# Power_module.net
KiCad netlist of a schematic drawn in EAGLE
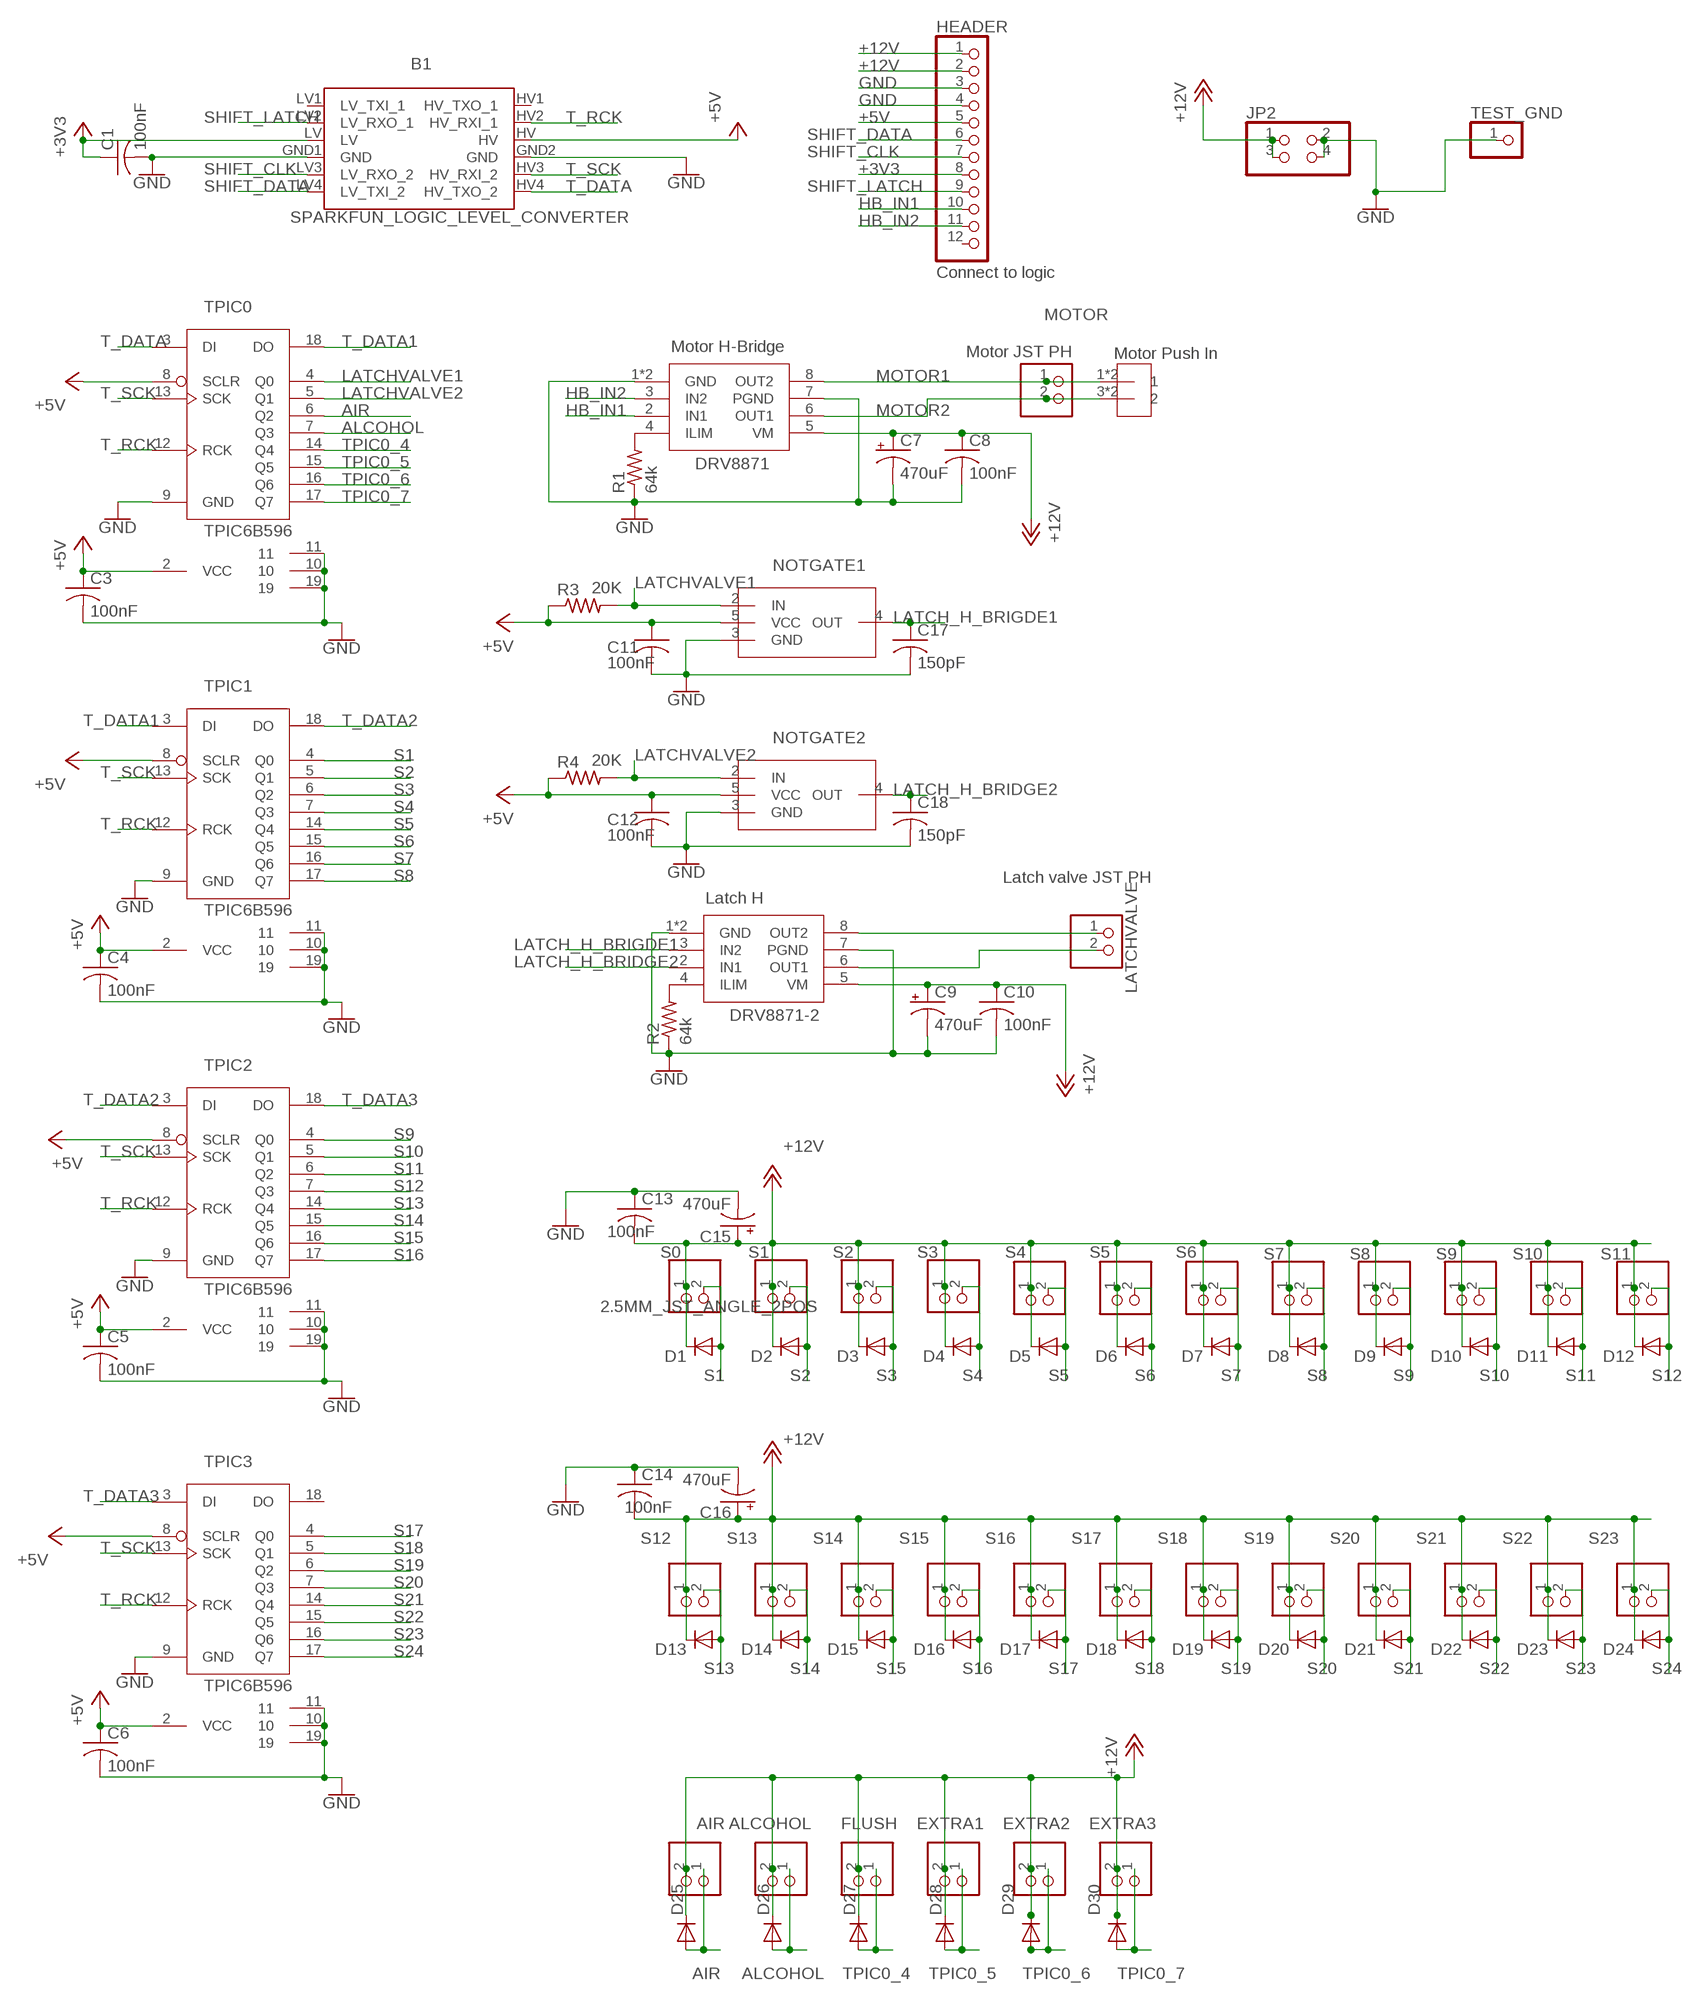
[diagram p0: schematic, sheet 1]

(export (version "E")
  (design (tool "Eeschema 10.0.6"))
  (components
    (comp (ref "AIR")
      (value "2.5MM_JST_UP_2POS")
      (footprint "eagle-import:JST_2POS_2.5MM_UP")
      (libsource (lib "eagle-import") (part "2.5MM_JST_UP_2POS"))
    )
    (comp (ref "ALCOHOL")
      (value "2.5MM_JST_UP_2POS")
      (footprint "eagle-import:JST_2POS_2.5MM_UP")
      (libsource (lib "eagle-import") (part "2.5MM_JST_UP_2POS"))
    )
    (comp (ref "B1")
      (value "SPARKFUN_LOGIC_LEVEL_CONVERTER")
      (footprint "eagle-import:SPARKFUN_LOGIC_LEVEL_CONVERTER")
      (libsource (lib "eagle-import") (part "SPARKFUN_LOGIC_LEVEL_CONVERTER"))
    )
    (comp (ref "C1")
      (value "100nF")
      (footprint "eagle-import:C050-024X044")
      (libsource (lib "eagle-import") (part "C-US050-024X044"))
    )
    (comp (ref "C3")
      (value "100nF")
      (footprint "eagle-import:C050-024X044")
      (libsource (lib "eagle-import") (part "C-US050-024X044"))
    )
    (comp (ref "C4")
      (value "100nF")
      (footprint "eagle-import:C050-024X044")
      (libsource (lib "eagle-import") (part "C-US050-024X044"))
    )
    (comp (ref "C5")
      (value "100nF")
      (footprint "eagle-import:C050-024X044")
      (libsource (lib "eagle-import") (part "C-US050-024X044"))
    )
    (comp (ref "C6")
      (value "100nF")
      (footprint "eagle-import:C050-024X044")
      (libsource (lib "eagle-import") (part "C-US050-024X044"))
    )
    (comp (ref "C7")
      (value "470uF")
      (footprint "eagle-import:140CLH-0810")
      (libsource (lib "eagle-import") (part "CPOL-US140CLH-0810"))
    )
    (comp (ref "C8")
      (value "100nF")
      (footprint "eagle-import:C050-024X044")
      (libsource (lib "eagle-import") (part "C-US050-024X044"))
    )
    (comp (ref "C9")
      (value "470uF")
      (footprint "eagle-import:140CLH-0810")
      (libsource (lib "eagle-import") (part "CPOL-US140CLH-0810"))
    )
    (comp (ref "C10")
      (value "100nF")
      (footprint "eagle-import:C050-024X044")
      (libsource (lib "eagle-import") (part "C-US050-024X044"))
    )
    (comp (ref "C11")
      (value "100nF")
      (footprint "eagle-import:C1206")
      (libsource (lib "eagle-import") (part "C-USC1206"))
    )
    (comp (ref "C12")
      (value "100nF")
      (footprint "eagle-import:C1206")
      (libsource (lib "eagle-import") (part "C-USC1206"))
    )
    (comp (ref "C13")
      (value "100nF")
      (footprint "eagle-import:C050-024X044")
      (libsource (lib "eagle-import") (part "C-US050-024X044"))
    )
    (comp (ref "C14")
      (value "100nF")
      (footprint "eagle-import:C050-024X044")
      (libsource (lib "eagle-import") (part "C-US050-024X044"))
    )
    (comp (ref "C15")
      (value "470uF")
      (footprint "eagle-import:140CLH-0810")
      (libsource (lib "eagle-import") (part "CPOL-US140CLH-0810"))
    )
    (comp (ref "C16")
      (value "470uF")
      (footprint "eagle-import:140CLH-0810")
      (libsource (lib "eagle-import") (part "CPOL-US140CLH-0810"))
    )
    (comp (ref "C17")
      (value "150pF")
      (footprint "eagle-import:C050-024X044")
      (libsource (lib "eagle-import") (part "C-US050-024X044"))
    )
    (comp (ref "C18")
      (value "150pF")
      (footprint "eagle-import:C050-024X044")
      (libsource (lib "eagle-import") (part "C-US050-024X044"))
    )
    (comp (ref "D1")
      (value "DIODESOD-123")
      (footprint "eagle-import:SOD-123")
      (libsource (lib "eagle-import") (part "DIODESOD-123"))
    )
    (comp (ref "D2")
      (value "DIODESOD-123")
      (footprint "eagle-import:SOD-123")
      (libsource (lib "eagle-import") (part "DIODESOD-123"))
    )
    (comp (ref "D3")
      (value "DIODESOD-123")
      (footprint "eagle-import:SOD-123")
      (libsource (lib "eagle-import") (part "DIODESOD-123"))
    )
    (comp (ref "D4")
      (value "DIODESOD-123")
      (footprint "eagle-import:SOD-123")
      (libsource (lib "eagle-import") (part "DIODESOD-123"))
    )
    (comp (ref "D5")
      (value "DIODESOD-123")
      (footprint "eagle-import:SOD-123")
      (libsource (lib "eagle-import") (part "DIODESOD-123"))
    )
    (comp (ref "D6")
      (value "DIODESOD-123")
      (footprint "eagle-import:SOD-123")
      (libsource (lib "eagle-import") (part "DIODESOD-123"))
    )
    (comp (ref "D7")
      (value "DIODESOD-123")
      (footprint "eagle-import:SOD-123")
      (libsource (lib "eagle-import") (part "DIODESOD-123"))
    )
    (comp (ref "D8")
      (value "DIODESOD-123")
      (footprint "eagle-import:SOD-123")
      (libsource (lib "eagle-import") (part "DIODESOD-123"))
    )
    (comp (ref "D9")
      (value "DIODESOD-123")
      (footprint "eagle-import:SOD-123")
      (libsource (lib "eagle-import") (part "DIODESOD-123"))
    )
    (comp (ref "D10")
      (value "DIODESOD-123")
      (footprint "eagle-import:SOD-123")
      (libsource (lib "eagle-import") (part "DIODESOD-123"))
    )
    (comp (ref "D11")
      (value "DIODESOD-123")
      (footprint "eagle-import:SOD-123")
      (libsource (lib "eagle-import") (part "DIODESOD-123"))
    )
    (comp (ref "D12")
      (value "DIODESOD-123")
      (footprint "eagle-import:SOD-123")
      (libsource (lib "eagle-import") (part "DIODESOD-123"))
    )
    (comp (ref "D13")
      (value "DIODESOD-123")
      (footprint "eagle-import:SOD-123")
      (libsource (lib "eagle-import") (part "DIODESOD-123"))
    )
    (comp (ref "D14")
      (value "DIODESOD-123")
      (footprint "eagle-import:SOD-123")
      (libsource (lib "eagle-import") (part "DIODESOD-123"))
    )
    (comp (ref "D15")
      (value "DIODESOD-123")
      (footprint "eagle-import:SOD-123")
      (libsource (lib "eagle-import") (part "DIODESOD-123"))
    )
    (comp (ref "D16")
      (value "DIODESOD-123")
      (footprint "eagle-import:SOD-123")
      (libsource (lib "eagle-import") (part "DIODESOD-123"))
    )
    (comp (ref "D17")
      (value "DIODESOD-123")
      (footprint "eagle-import:SOD-123")
      (libsource (lib "eagle-import") (part "DIODESOD-123"))
    )
    (comp (ref "D18")
      (value "DIODESOD-123")
      (footprint "eagle-import:SOD-123")
      (libsource (lib "eagle-import") (part "DIODESOD-123"))
    )
    (comp (ref "D19")
      (value "DIODESOD-123")
      (footprint "eagle-import:SOD-123")
      (libsource (lib "eagle-import") (part "DIODESOD-123"))
    )
    (comp (ref "D20")
      (value "DIODESOD-123")
      (footprint "eagle-import:SOD-123")
      (libsource (lib "eagle-import") (part "DIODESOD-123"))
    )
    (comp (ref "D21")
      (value "DIODESOD-123")
      (footprint "eagle-import:SOD-123")
      (libsource (lib "eagle-import") (part "DIODESOD-123"))
    )
    (comp (ref "D22")
      (value "DIODESOD-123")
      (footprint "eagle-import:SOD-123")
      (libsource (lib "eagle-import") (part "DIODESOD-123"))
    )
    (comp (ref "D23")
      (value "DIODESOD-123")
      (footprint "eagle-import:SOD-123")
      (libsource (lib "eagle-import") (part "DIODESOD-123"))
    )
    (comp (ref "D24")
      (value "DIODESOD-123")
      (footprint "eagle-import:SOD-123")
      (libsource (lib "eagle-import") (part "DIODESOD-123"))
    )
    (comp (ref "D25")
      (value "DIODESOD-123")
      (footprint "eagle-import:SOD-123")
      (libsource (lib "eagle-import") (part "DIODESOD-123"))
    )
    (comp (ref "D26")
      (value "DIODESOD-123")
      (footprint "eagle-import:SOD-123")
      (libsource (lib "eagle-import") (part "DIODESOD-123"))
    )
    (comp (ref "D27")
      (value "DIODESOD-123")
      (footprint "eagle-import:SOD-123")
      (libsource (lib "eagle-import") (part "DIODESOD-123"))
    )
    (comp (ref "D28")
      (value "DIODESOD-123")
      (footprint "eagle-import:SOD-123")
      (libsource (lib "eagle-import") (part "DIODESOD-123"))
    )
    (comp (ref "D29")
      (value "DIODESOD-123")
      (footprint "eagle-import:SOD-123")
      (libsource (lib "eagle-import") (part "DIODESOD-123"))
    )
    (comp (ref "D30")
      (value "DIODESOD-123")
      (footprint "eagle-import:SOD-123")
      (libsource (lib "eagle-import") (part "DIODESOD-123"))
    )
    (comp (ref "DRV8871")
      (value "Motor H-Bridge")
      (footprint "eagle-import:SOP8")
      (libsource (lib "eagle-import") (part "DRV8871"))
    )
    (comp (ref "DRV8871-2")
      (value "Latch H")
      (footprint "eagle-import:SOP8")
      (libsource (lib "eagle-import") (part "DRV8871"))
    )
    (comp (ref "EXTRA1")
      (value "2.5MM_JST_UP_2POS")
      (footprint "eagle-import:JST_2POS_2.5MM_UP")
      (libsource (lib "eagle-import") (part "2.5MM_JST_UP_2POS"))
    )
    (comp (ref "EXTRA2")
      (value "2.5MM_JST_UP_2POS")
      (footprint "eagle-import:JST_2POS_2.5MM_UP")
      (libsource (lib "eagle-import") (part "2.5MM_JST_UP_2POS"))
    )
    (comp (ref "EXTRA3")
      (value "2.5MM_JST_UP_2POS")
      (footprint "eagle-import:JST_2POS_2.5MM_UP")
      (libsource (lib "eagle-import") (part "2.5MM_JST_UP_2POS"))
    )
    (comp (ref "FLUSH")
      (value "2.5MM_JST_UP_2POS")
      (footprint "eagle-import:JST_2POS_2.5MM_UP")
      (libsource (lib "eagle-import") (part "2.5MM_JST_UP_2POS"))
    )
    (comp (ref "HEADER")
      (value "Connect to logic")
      (footprint "eagle-import:1X12")
      (libsource (lib "eagle-import") (part "PINHD-1X12"))
    )
    (comp (ref "JP2")
      (value "PINHD-2X2")
      (footprint "eagle-import:2X02")
      (libsource (lib "eagle-import") (part "PINHD-2X2"))
    )
    (comp (ref "LATCHVALVE")
      (value "Latch valve JST PH")
      (footprint "eagle-import:JST_2POS_2.5MM_UP")
      (libsource (lib "eagle-import") (part "2.5MM_JST_UP_2POS"))
    )
    (comp (ref "MOTOR")
      (value "Motor JST PH")
      (footprint "eagle-import:JST_2POS_2.5MM_UP")
      (libsource (lib "eagle-import") (part "2.5MM_JST_UP_2POS"))
    )
    (comp (ref "NOTGATE1")
      (value "NOT_GATE")
      (footprint "eagle-import:SOT753")
      (libsource (lib "eagle-import") (part "NOT_GATE"))
    )
    (comp (ref "NOTGATE2")
      (value "NOT_GATE")
      (footprint "eagle-import:SOT753")
      (libsource (lib "eagle-import") (part "NOT_GATE"))
    )
    (comp (ref "R1")
      (value "64k")
      (footprint "eagle-import:0204_5")
      (libsource (lib "eagle-import") (part "R-US_0204/5"))
    )
    (comp (ref "R2")
      (value "64k")
      (footprint "eagle-import:0204_5")
      (libsource (lib "eagle-import") (part "R-US_0204/5"))
    )
    (comp (ref "R3")
      (value "20K")
      (footprint "eagle-import:R1206")
      (libsource (lib "eagle-import") (part "R-US_R1206"))
    )
    (comp (ref "R4")
      (value "20K")
      (footprint "eagle-import:R1206")
      (libsource (lib "eagle-import") (part "R-US_R1206"))
    )
    (comp (ref "S0")
      (value "2.5MM_JST_ANGLE_2POS")
      (footprint "eagle-import:JST_2POS_2.5MM_ANGLE")
      (libsource (lib "eagle-import") (part "2.5MM_JST_ANGLE_2POS"))
    )
    (comp (ref "S1")
      (value "2.5MM_JST_ANGLE_2POS")
      (footprint "eagle-import:JST_2POS_2.5MM_ANGLE")
      (libsource (lib "eagle-import") (part "2.5MM_JST_ANGLE_2POS"))
    )
    (comp (ref "S2")
      (value "2.5MM_JST_ANGLE_2POS")
      (footprint "eagle-import:JST_2POS_2.5MM_ANGLE")
      (libsource (lib "eagle-import") (part "2.5MM_JST_ANGLE_2POS"))
    )
    (comp (ref "S3")
      (value "2.5MM_JST_ANGLE_2POS")
      (footprint "eagle-import:JST_2POS_2.5MM_ANGLE")
      (libsource (lib "eagle-import") (part "2.5MM_JST_ANGLE_2POS"))
    )
    (comp (ref "S4")
      (value "2.5MM_JST_ANGLE_2POS")
      (footprint "eagle-import:JST_2POS_2.5MM_ANGLE")
      (libsource (lib "eagle-import") (part "2.5MM_JST_ANGLE_2POS"))
    )
    (comp (ref "S5")
      (value "2.5MM_JST_ANGLE_2POS")
      (footprint "eagle-import:JST_2POS_2.5MM_ANGLE")
      (libsource (lib "eagle-import") (part "2.5MM_JST_ANGLE_2POS"))
    )
    (comp (ref "S6")
      (value "2.5MM_JST_ANGLE_2POS")
      (footprint "eagle-import:JST_2POS_2.5MM_ANGLE")
      (libsource (lib "eagle-import") (part "2.5MM_JST_ANGLE_2POS"))
    )
    (comp (ref "S7")
      (value "2.5MM_JST_ANGLE_2POS")
      (footprint "eagle-import:JST_2POS_2.5MM_ANGLE")
      (libsource (lib "eagle-import") (part "2.5MM_JST_ANGLE_2POS"))
    )
    (comp (ref "S8")
      (value "2.5MM_JST_ANGLE_2POS")
      (footprint "eagle-import:JST_2POS_2.5MM_ANGLE")
      (libsource (lib "eagle-import") (part "2.5MM_JST_ANGLE_2POS"))
    )
    (comp (ref "S9")
      (value "2.5MM_JST_ANGLE_2POS")
      (footprint "eagle-import:JST_2POS_2.5MM_ANGLE")
      (libsource (lib "eagle-import") (part "2.5MM_JST_ANGLE_2POS"))
    )
    (comp (ref "S10")
      (value "2.5MM_JST_ANGLE_2POS")
      (footprint "eagle-import:JST_2POS_2.5MM_ANGLE")
      (libsource (lib "eagle-import") (part "2.5MM_JST_ANGLE_2POS"))
    )
    (comp (ref "S11")
      (value "2.5MM_JST_ANGLE_2POS")
      (footprint "eagle-import:JST_2POS_2.5MM_ANGLE")
      (libsource (lib "eagle-import") (part "2.5MM_JST_ANGLE_2POS"))
    )
    (comp (ref "S12")
      (value "2.5MM_JST_ANGLE_2POS")
      (footprint "eagle-import:JST_2POS_2.5MM_ANGLE")
      (libsource (lib "eagle-import") (part "2.5MM_JST_ANGLE_2POS"))
    )
    (comp (ref "S13")
      (value "2.5MM_JST_ANGLE_2POS")
      (footprint "eagle-import:JST_2POS_2.5MM_ANGLE")
      (libsource (lib "eagle-import") (part "2.5MM_JST_ANGLE_2POS"))
    )
    (comp (ref "S14")
      (value "2.5MM_JST_ANGLE_2POS")
      (footprint "eagle-import:JST_2POS_2.5MM_ANGLE")
      (libsource (lib "eagle-import") (part "2.5MM_JST_ANGLE_2POS"))
    )
    (comp (ref "S15")
      (value "2.5MM_JST_ANGLE_2POS")
      (footprint "eagle-import:JST_2POS_2.5MM_ANGLE")
      (libsource (lib "eagle-import") (part "2.5MM_JST_ANGLE_2POS"))
    )
    (comp (ref "S16")
      (value "2.5MM_JST_ANGLE_2POS")
      (footprint "eagle-import:JST_2POS_2.5MM_ANGLE")
      (libsource (lib "eagle-import") (part "2.5MM_JST_ANGLE_2POS"))
    )
    (comp (ref "S17")
      (value "2.5MM_JST_ANGLE_2POS")
      (footprint "eagle-import:JST_2POS_2.5MM_ANGLE")
      (libsource (lib "eagle-import") (part "2.5MM_JST_ANGLE_2POS"))
    )
    (comp (ref "S18")
      (value "2.5MM_JST_ANGLE_2POS")
      (footprint "eagle-import:JST_2POS_2.5MM_ANGLE")
      (libsource (lib "eagle-import") (part "2.5MM_JST_ANGLE_2POS"))
    )
    (comp (ref "S19")
      (value "2.5MM_JST_ANGLE_2POS")
      (footprint "eagle-import:JST_2POS_2.5MM_ANGLE")
      (libsource (lib "eagle-import") (part "2.5MM_JST_ANGLE_2POS"))
    )
    (comp (ref "S20")
      (value "2.5MM_JST_ANGLE_2POS")
      (footprint "eagle-import:JST_2POS_2.5MM_ANGLE")
      (libsource (lib "eagle-import") (part "2.5MM_JST_ANGLE_2POS"))
    )
    (comp (ref "S21")
      (value "2.5MM_JST_ANGLE_2POS")
      (footprint "eagle-import:JST_2POS_2.5MM_ANGLE")
      (libsource (lib "eagle-import") (part "2.5MM_JST_ANGLE_2POS"))
    )
    (comp (ref "S22")
      (value "2.5MM_JST_ANGLE_2POS")
      (footprint "eagle-import:JST_2POS_2.5MM_ANGLE")
      (libsource (lib "eagle-import") (part "2.5MM_JST_ANGLE_2POS"))
    )
    (comp (ref "S23")
      (value "2.5MM_JST_ANGLE_2POS")
      (footprint "eagle-import:JST_2POS_2.5MM_ANGLE")
      (libsource (lib "eagle-import") (part "2.5MM_JST_ANGLE_2POS"))
    )
    (comp (ref "TEST_GND")
      (value "PINHD-1X1")
      (footprint "eagle-import:1X01")
      (libsource (lib "eagle-import") (part "PINHD-1X1"))
    )
    (comp (ref "TPIC0")
      (value "TPIC6B596")
      (footprint "eagle-import:DIP20")
      (libsource (lib "eagle-import") (part "TPIC6B596"))
    )
    (comp (ref "TPIC1")
      (value "TPIC6B596")
      (footprint "eagle-import:DIP20")
      (libsource (lib "eagle-import") (part "TPIC6B596"))
    )
    (comp (ref "TPIC2")
      (value "TPIC6B596")
      (footprint "eagle-import:DIP20")
      (libsource (lib "eagle-import") (part "TPIC6B596"))
    )
    (comp (ref "TPIC3")
      (value "TPIC6B596")
      (footprint "eagle-import:DIP20")
      (libsource (lib "eagle-import") (part "TPIC6B596"))
    )
    (comp (ref "U$1")
      (value "Motor Push In")
      (footprint "eagle-import:3.5MM_DIP2")
      (libsource (lib "eagle-import") (part "PUSH_IN_2"))
    )
  )
  (nets
    (net (code "1") (name "+3V3") (class "Default")
      (node (ref "B1") (pin "LV") (pinfunction "LV_LV") (pintype "power_in"))
      (node (ref "C1") (pin "1") (pinfunction "1_1") (pintype "passive"))
      (node (ref "HEADER") (pin "8") (pinfunction "8_8") (pintype "passive"))
    )
    (net (code "2") (name "+5V") (class "Default")
      (node (ref "B1") (pin "HV") (pinfunction "HV_HV") (pintype "power_in"))
      (node (ref "C11") (pin "1") (pinfunction "1_1") (pintype "passive"))
      (node (ref "C12") (pin "1") (pinfunction "1_1") (pintype "passive"))
      (node (ref "C3") (pin "1") (pinfunction "1_1") (pintype "passive"))
      (node (ref "C4") (pin "1") (pinfunction "1_1") (pintype "passive"))
      (node (ref "C5") (pin "1") (pinfunction "1_1") (pintype "passive"))
      (node (ref "C6") (pin "1") (pinfunction "1_1") (pintype "passive"))
      (node (ref "HEADER") (pin "5") (pinfunction "5_5") (pintype "passive"))
      (node (ref "NOTGATE1") (pin "5") (pinfunction "VCC_5") (pintype "bidirectional"))
      (node (ref "NOTGATE2") (pin "5") (pinfunction "VCC_5") (pintype "bidirectional"))
      (node (ref "R3") (pin "1") (pinfunction "1_1") (pintype "passive"))
      (node (ref "R4") (pin "1") (pinfunction "1_1") (pintype "passive"))
      (node (ref "TPIC0") (pin "2") (pinfunction "VCC_2") (pintype "bidirectional"))
      (node (ref "TPIC0") (pin "8") (pinfunction "SCLR_8") (pintype "bidirectional"))
      (node (ref "TPIC1") (pin "2") (pinfunction "VCC_2") (pintype "bidirectional"))
      (node (ref "TPIC1") (pin "8") (pinfunction "SCLR_8") (pintype "bidirectional"))
      (node (ref "TPIC2") (pin "2") (pinfunction "VCC_2") (pintype "bidirectional"))
      (node (ref "TPIC2") (pin "8") (pinfunction "SCLR_8") (pintype "bidirectional"))
      (node (ref "TPIC3") (pin "2") (pinfunction "VCC_2") (pintype "bidirectional"))
      (node (ref "TPIC3") (pin "8") (pinfunction "SCLR_8") (pintype "bidirectional"))
    )
    (net (code "3") (name "+12V") (class "Default")
      (node (ref "AIR") (pin "2") (pinfunction "2_2") (pintype "bidirectional"))
      (node (ref "ALCOHOL") (pin "2") (pinfunction "2_2") (pintype "bidirectional"))
      (node (ref "C10") (pin "1") (pinfunction "1_1") (pintype "passive"))
      (node (ref "C13") (pin "2") (pinfunction "2_2") (pintype "passive"))
      (node (ref "C14") (pin "2") (pinfunction "2_2") (pintype "passive"))
      (node (ref "C15") (pin "+") (pinfunction "+_+") (pintype "passive"))
      (node (ref "C16") (pin "+") (pinfunction "+_+") (pintype "passive"))
      (node (ref "C7") (pin "+") (pinfunction "+_+") (pintype "passive"))
      (node (ref "C8") (pin "1") (pinfunction "1_1") (pintype "passive"))
      (node (ref "C9") (pin "+") (pinfunction "+_+") (pintype "passive"))
      (node (ref "D1") (pin "C") (pinfunction "C_C") (pintype "passive"))
      (node (ref "D10") (pin "C") (pinfunction "C_C") (pintype "passive"))
      (node (ref "D11") (pin "C") (pinfunction "C_C") (pintype "passive"))
      (node (ref "D12") (pin "C") (pinfunction "C_C") (pintype "passive"))
      (node (ref "D13") (pin "C") (pinfunction "C_C") (pintype "passive"))
      (node (ref "D14") (pin "C") (pinfunction "C_C") (pintype "passive"))
      (node (ref "D15") (pin "C") (pinfunction "C_C") (pintype "passive"))
      (node (ref "D16") (pin "C") (pinfunction "C_C") (pintype "passive"))
      (node (ref "D17") (pin "C") (pinfunction "C_C") (pintype "passive"))
      (node (ref "D18") (pin "C") (pinfunction "C_C") (pintype "passive"))
      (node (ref "D19") (pin "C") (pinfunction "C_C") (pintype "passive"))
      (node (ref "D2") (pin "C") (pinfunction "C_C") (pintype "passive"))
      (node (ref "D20") (pin "C") (pinfunction "C_C") (pintype "passive"))
      (node (ref "D21") (pin "C") (pinfunction "C_C") (pintype "passive"))
      (node (ref "D22") (pin "C") (pinfunction "C_C") (pintype "passive"))
      (node (ref "D23") (pin "C") (pinfunction "C_C") (pintype "passive"))
      (node (ref "D24") (pin "C") (pinfunction "C_C") (pintype "passive"))
      (node (ref "D25") (pin "C") (pinfunction "C_C") (pintype "passive"))
      (node (ref "D26") (pin "C") (pinfunction "C_C") (pintype "passive"))
      (node (ref "D27") (pin "C") (pinfunction "C_C") (pintype "passive"))
      (node (ref "D28") (pin "C") (pinfunction "C_C") (pintype "passive"))
      (node (ref "D29") (pin "C") (pinfunction "C_C") (pintype "passive"))
      (node (ref "D3") (pin "C") (pinfunction "C_C") (pintype "passive"))
      (node (ref "D30") (pin "C") (pinfunction "C_C") (pintype "passive"))
      (node (ref "D4") (pin "C") (pinfunction "C_C") (pintype "passive"))
      (node (ref "D5") (pin "C") (pinfunction "C_C") (pintype "passive"))
      (node (ref "D6") (pin "C") (pinfunction "C_C") (pintype "passive"))
      (node (ref "D7") (pin "C") (pinfunction "C_C") (pintype "passive"))
      (node (ref "D8") (pin "C") (pinfunction "C_C") (pintype "passive"))
      (node (ref "D9") (pin "C") (pinfunction "C_C") (pintype "passive"))
      (node (ref "DRV8871") (pin "5") (pinfunction "VM_5") (pintype "bidirectional"))
      (node (ref "DRV8871-2") (pin "5") (pinfunction "VM_5") (pintype "bidirectional"))
      (node (ref "EXTRA1") (pin "2") (pinfunction "2_2") (pintype "bidirectional"))
      (node (ref "EXTRA2") (pin "2") (pinfunction "2_2") (pintype "bidirectional"))
      (node (ref "EXTRA3") (pin "2") (pinfunction "2_2") (pintype "bidirectional"))
      (node (ref "FLUSH") (pin "2") (pinfunction "2_2") (pintype "bidirectional"))
      (node (ref "HEADER") (pin "1") (pinfunction "1_1") (pintype "passive"))
      (node (ref "HEADER") (pin "2") (pinfunction "2_2") (pintype "passive"))
      (node (ref "JP2") (pin "1") (pinfunction "1_1") (pintype "passive"))
      (node (ref "JP2") (pin "3") (pinfunction "3_3") (pintype "passive"))
      (node (ref "S0") (pin "1") (pinfunction "2_1") (pintype "bidirectional"))
      (node (ref "S1") (pin "1") (pinfunction "2_1") (pintype "bidirectional"))
      (node (ref "S10") (pin "1") (pinfunction "2_1") (pintype "bidirectional"))
      (node (ref "S11") (pin "1") (pinfunction "2_1") (pintype "bidirectional"))
      (node (ref "S12") (pin "1") (pinfunction "2_1") (pintype "bidirectional"))
      (node (ref "S13") (pin "1") (pinfunction "2_1") (pintype "bidirectional"))
      (node (ref "S14") (pin "1") (pinfunction "2_1") (pintype "bidirectional"))
      (node (ref "S15") (pin "1") (pinfunction "2_1") (pintype "bidirectional"))
      (node (ref "S16") (pin "1") (pinfunction "2_1") (pintype "bidirectional"))
      (node (ref "S17") (pin "1") (pinfunction "2_1") (pintype "bidirectional"))
      (node (ref "S18") (pin "1") (pinfunction "2_1") (pintype "bidirectional"))
      (node (ref "S19") (pin "1") (pinfunction "2_1") (pintype "bidirectional"))
      (node (ref "S2") (pin "1") (pinfunction "2_1") (pintype "bidirectional"))
      (node (ref "S20") (pin "1") (pinfunction "2_1") (pintype "bidirectional"))
      (node (ref "S21") (pin "1") (pinfunction "2_1") (pintype "bidirectional"))
      (node (ref "S22") (pin "1") (pinfunction "2_1") (pintype "bidirectional"))
      (node (ref "S23") (pin "1") (pinfunction "2_1") (pintype "bidirectional"))
      (node (ref "S3") (pin "1") (pinfunction "2_1") (pintype "bidirectional"))
      (node (ref "S4") (pin "1") (pinfunction "2_1") (pintype "bidirectional"))
      (node (ref "S5") (pin "1") (pinfunction "2_1") (pintype "bidirectional"))
      (node (ref "S6") (pin "1") (pinfunction "2_1") (pintype "bidirectional"))
      (node (ref "S7") (pin "1") (pinfunction "2_1") (pintype "bidirectional"))
      (node (ref "S8") (pin "1") (pinfunction "2_1") (pintype "bidirectional"))
      (node (ref "S9") (pin "1") (pinfunction "2_1") (pintype "bidirectional"))
    )
    (net (code "4") (name "/AIR") (class "Default")
      (node (ref "AIR") (pin "1") (pinfunction "1_1") (pintype "bidirectional"))
      (node (ref "D25") (pin "A") (pinfunction "A_A") (pintype "passive"))
      (node (ref "TPIC0") (pin "6") (pinfunction "Q2_6") (pintype "bidirectional"))
    )
    (net (code "5") (name "/ALCOHOL") (class "Default")
      (node (ref "ALCOHOL") (pin "1") (pinfunction "1_1") (pintype "bidirectional"))
      (node (ref "D26") (pin "A") (pinfunction "A_A") (pintype "passive"))
      (node (ref "TPIC0") (pin "7") (pinfunction "Q3_7") (pintype "bidirectional"))
    )
    (net (code "6") (name "/HB_IN1") (class "Default")
      (node (ref "DRV8871") (pin "2") (pinfunction "IN1_2") (pintype "bidirectional"))
      (node (ref "HEADER") (pin "10") (pinfunction "10_10") (pintype "passive"))
    )
    (net (code "7") (name "/HB_IN2") (class "Default")
      (node (ref "DRV8871") (pin "3") (pinfunction "IN2_3") (pintype "bidirectional"))
      (node (ref "HEADER") (pin "11") (pinfunction "11_11") (pintype "passive"))
    )
    (net (code "8") (name "/LATCHVALVE1") (class "Default")
      (node (ref "NOTGATE1") (pin "2") (pinfunction "IN_2") (pintype "bidirectional"))
      (node (ref "R3") (pin "2") (pinfunction "2_2") (pintype "passive"))
      (node (ref "TPIC0") (pin "4") (pinfunction "Q0_4") (pintype "bidirectional"))
    )
    (net (code "9") (name "/LATCHVALVE2") (class "Default")
      (node (ref "NOTGATE2") (pin "2") (pinfunction "IN_2") (pintype "bidirectional"))
      (node (ref "R4") (pin "2") (pinfunction "2_2") (pintype "passive"))
      (node (ref "TPIC0") (pin "5") (pinfunction "Q1_5") (pintype "bidirectional"))
    )
    (net (code "10") (name "/LATCH_H_BRIDGE2") (class "Default")
      (node (ref "C18") (pin "1") (pinfunction "1_1") (pintype "passive"))
      (node (ref "DRV8871-2") (pin "2") (pinfunction "IN1_2") (pintype "bidirectional"))
      (node (ref "NOTGATE2") (pin "4") (pinfunction "OUT_4") (pintype "bidirectional"))
    )
    (net (code "11") (name "/LATCH_H_BRIGDE1") (class "Default")
      (node (ref "C17") (pin "1") (pinfunction "1_1") (pintype "passive"))
      (node (ref "DRV8871-2") (pin "3") (pinfunction "IN2_3") (pintype "bidirectional"))
      (node (ref "NOTGATE1") (pin "4") (pinfunction "OUT_4") (pintype "bidirectional"))
    )
    (net (code "12") (name "/MOTOR1") (class "Default")
      (node (ref "DRV8871") (pin "8") (pinfunction "OUT2_8") (pintype "bidirectional"))
      (node (ref "MOTOR") (pin "1") (pinfunction "1_1") (pintype "bidirectional"))
      (node (ref "U$1") (pin "1") (pinfunction "1_1") (pintype "bidirectional"))
      (node (ref "U$1") (pin "2") (pinfunction "1_2") (pintype "bidirectional"))
    )
    (net (code "13") (name "/MOTOR2") (class "Default")
      (node (ref "DRV8871") (pin "6") (pinfunction "OUT1_6") (pintype "bidirectional"))
      (node (ref "MOTOR") (pin "2") (pinfunction "2_2") (pintype "bidirectional"))
      (node (ref "U$1") (pin "3") (pinfunction "2_3") (pintype "bidirectional"))
      (node (ref "U$1") (pin "4") (pinfunction "2_4") (pintype "bidirectional"))
    )
    (net (code "14") (name "/S1") (class "Default")
      (node (ref "D1") (pin "A") (pinfunction "A_A") (pintype "passive"))
      (node (ref "S0") (pin "2") (pinfunction "1_2") (pintype "bidirectional"))
      (node (ref "TPIC1") (pin "4") (pinfunction "Q0_4") (pintype "bidirectional"))
    )
    (net (code "15") (name "/S2") (class "Default")
      (node (ref "D2") (pin "A") (pinfunction "A_A") (pintype "passive"))
      (node (ref "S1") (pin "2") (pinfunction "1_2") (pintype "bidirectional"))
      (node (ref "TPIC1") (pin "5") (pinfunction "Q1_5") (pintype "bidirectional"))
    )
    (net (code "16") (name "/S3") (class "Default")
      (node (ref "D3") (pin "A") (pinfunction "A_A") (pintype "passive"))
      (node (ref "S2") (pin "2") (pinfunction "1_2") (pintype "bidirectional"))
      (node (ref "TPIC1") (pin "6") (pinfunction "Q2_6") (pintype "bidirectional"))
    )
    (net (code "17") (name "/S4") (class "Default")
      (node (ref "D4") (pin "A") (pinfunction "A_A") (pintype "passive"))
      (node (ref "S3") (pin "2") (pinfunction "1_2") (pintype "bidirectional"))
      (node (ref "TPIC1") (pin "7") (pinfunction "Q3_7") (pintype "bidirectional"))
    )
    (net (code "18") (name "/S5") (class "Default")
      (node (ref "D5") (pin "A") (pinfunction "A_A") (pintype "passive"))
      (node (ref "S4") (pin "2") (pinfunction "1_2") (pintype "bidirectional"))
      (node (ref "TPIC1") (pin "14") (pinfunction "Q4_14") (pintype "bidirectional"))
    )
    (net (code "19") (name "/S6") (class "Default")
      (node (ref "D6") (pin "A") (pinfunction "A_A") (pintype "passive"))
      (node (ref "S5") (pin "2") (pinfunction "1_2") (pintype "bidirectional"))
      (node (ref "TPIC1") (pin "15") (pinfunction "Q5_15") (pintype "bidirectional"))
    )
    (net (code "20") (name "/S7") (class "Default")
      (node (ref "D7") (pin "A") (pinfunction "A_A") (pintype "passive"))
      (node (ref "S6") (pin "2") (pinfunction "1_2") (pintype "bidirectional"))
      (node (ref "TPIC1") (pin "16") (pinfunction "Q6_16") (pintype "bidirectional"))
    )
    (net (code "21") (name "/S8") (class "Default")
      (node (ref "D8") (pin "A") (pinfunction "A_A") (pintype "passive"))
      (node (ref "S7") (pin "2") (pinfunction "1_2") (pintype "bidirectional"))
      (node (ref "TPIC1") (pin "17") (pinfunction "Q7_17") (pintype "bidirectional"))
    )
    (net (code "22") (name "/S9") (class "Default")
      (node (ref "D9") (pin "A") (pinfunction "A_A") (pintype "passive"))
      (node (ref "S8") (pin "2") (pinfunction "1_2") (pintype "bidirectional"))
      (node (ref "TPIC2") (pin "4") (pinfunction "Q0_4") (pintype "bidirectional"))
    )
    (net (code "23") (name "/S10") (class "Default")
      (node (ref "D10") (pin "A") (pinfunction "A_A") (pintype "passive"))
      (node (ref "S9") (pin "2") (pinfunction "1_2") (pintype "bidirectional"))
      (node (ref "TPIC2") (pin "5") (pinfunction "Q1_5") (pintype "bidirectional"))
    )
    (net (code "24") (name "/S11") (class "Default")
      (node (ref "D11") (pin "A") (pinfunction "A_A") (pintype "passive"))
      (node (ref "S10") (pin "2") (pinfunction "1_2") (pintype "bidirectional"))
      (node (ref "TPIC2") (pin "6") (pinfunction "Q2_6") (pintype "bidirectional"))
    )
    (net (code "25") (name "/S12") (class "Default")
      (node (ref "D12") (pin "A") (pinfunction "A_A") (pintype "passive"))
      (node (ref "S11") (pin "2") (pinfunction "1_2") (pintype "bidirectional"))
      (node (ref "TPIC2") (pin "7") (pinfunction "Q3_7") (pintype "bidirectional"))
    )
    (net (code "26") (name "/S13") (class "Default")
      (node (ref "D13") (pin "A") (pinfunction "A_A") (pintype "passive"))
      (node (ref "S12") (pin "2") (pinfunction "1_2") (pintype "bidirectional"))
      (node (ref "TPIC2") (pin "14") (pinfunction "Q4_14") (pintype "bidirectional"))
    )
    (net (code "27") (name "/S14") (class "Default")
      (node (ref "D14") (pin "A") (pinfunction "A_A") (pintype "passive"))
      (node (ref "S13") (pin "2") (pinfunction "1_2") (pintype "bidirectional"))
      (node (ref "TPIC2") (pin "15") (pinfunction "Q5_15") (pintype "bidirectional"))
    )
    (net (code "28") (name "/S15") (class "Default")
      (node (ref "D15") (pin "A") (pinfunction "A_A") (pintype "passive"))
      (node (ref "S14") (pin "2") (pinfunction "1_2") (pintype "bidirectional"))
      (node (ref "TPIC2") (pin "16") (pinfunction "Q6_16") (pintype "bidirectional"))
    )
    (net (code "29") (name "/S16") (class "Default")
      (node (ref "D16") (pin "A") (pinfunction "A_A") (pintype "passive"))
      (node (ref "S15") (pin "2") (pinfunction "1_2") (pintype "bidirectional"))
      (node (ref "TPIC2") (pin "17") (pinfunction "Q7_17") (pintype "bidirectional"))
    )
    (net (code "30") (name "/S17") (class "Default")
      (node (ref "D17") (pin "A") (pinfunction "A_A") (pintype "passive"))
      (node (ref "S16") (pin "2") (pinfunction "1_2") (pintype "bidirectional"))
      (node (ref "TPIC3") (pin "4") (pinfunction "Q0_4") (pintype "bidirectional"))
    )
    (net (code "31") (name "/S18") (class "Default")
      (node (ref "D18") (pin "A") (pinfunction "A_A") (pintype "passive"))
      (node (ref "S17") (pin "2") (pinfunction "1_2") (pintype "bidirectional"))
      (node (ref "TPIC3") (pin "5") (pinfunction "Q1_5") (pintype "bidirectional"))
    )
    (net (code "32") (name "/S19") (class "Default")
      (node (ref "D19") (pin "A") (pinfunction "A_A") (pintype "passive"))
      (node (ref "S18") (pin "2") (pinfunction "1_2") (pintype "bidirectional"))
      (node (ref "TPIC3") (pin "6") (pinfunction "Q2_6") (pintype "bidirectional"))
    )
    (net (code "33") (name "/S20") (class "Default")
      (node (ref "D20") (pin "A") (pinfunction "A_A") (pintype "passive"))
      (node (ref "S19") (pin "2") (pinfunction "1_2") (pintype "bidirectional"))
      (node (ref "TPIC3") (pin "7") (pinfunction "Q3_7") (pintype "bidirectional"))
    )
    (net (code "34") (name "/S21") (class "Default")
      (node (ref "D21") (pin "A") (pinfunction "A_A") (pintype "passive"))
      (node (ref "S20") (pin "2") (pinfunction "1_2") (pintype "bidirectional"))
      (node (ref "TPIC3") (pin "14") (pinfunction "Q4_14") (pintype "bidirectional"))
    )
    (net (code "35") (name "/S22") (class "Default")
      (node (ref "D22") (pin "A") (pinfunction "A_A") (pintype "passive"))
      (node (ref "S21") (pin "2") (pinfunction "1_2") (pintype "bidirectional"))
      (node (ref "TPIC3") (pin "15") (pinfunction "Q5_15") (pintype "bidirectional"))
    )
    (net (code "36") (name "/S23") (class "Default")
      (node (ref "D23") (pin "A") (pinfunction "A_A") (pintype "passive"))
      (node (ref "S22") (pin "2") (pinfunction "1_2") (pintype "bidirectional"))
      (node (ref "TPIC3") (pin "16") (pinfunction "Q6_16") (pintype "bidirectional"))
    )
    (net (code "37") (name "/S24") (class "Default")
      (node (ref "D24") (pin "A") (pinfunction "A_A") (pintype "passive"))
      (node (ref "S23") (pin "2") (pinfunction "1_2") (pintype "bidirectional"))
      (node (ref "TPIC3") (pin "17") (pinfunction "Q7_17") (pintype "bidirectional"))
    )
    (net (code "38") (name "/SHIFT_CLK") (class "Default")
      (node (ref "B1") (pin "LV3") (pinfunction "LV_RXO_2_LV3") (pintype "bidirectional"))
      (node (ref "HEADER") (pin "7") (pinfunction "7_7") (pintype "passive"))
    )
    (net (code "39") (name "/SHIFT_DATA") (class "Default")
      (node (ref "B1") (pin "LV4") (pinfunction "LV_TXI_2_LV4") (pintype "bidirectional"))
      (node (ref "HEADER") (pin "6") (pinfunction "6_6") (pintype "passive"))
    )
    (net (code "40") (name "/SHIFT_LATCH") (class "Default")
      (node (ref "B1") (pin "LV2") (pinfunction "LV_RXO_1_LV2") (pintype "bidirectional"))
      (node (ref "HEADER") (pin "9") (pinfunction "9_9") (pintype "passive"))
    )
    (net (code "41") (name "/TPIC0_4") (class "Default")
      (node (ref "D27") (pin "A") (pinfunction "A_A") (pintype "passive"))
      (node (ref "FLUSH") (pin "1") (pinfunction "1_1") (pintype "bidirectional"))
      (node (ref "TPIC0") (pin "14") (pinfunction "Q4_14") (pintype "bidirectional"))
    )
    (net (code "42") (name "/TPIC0_5") (class "Default")
      (node (ref "D28") (pin "A") (pinfunction "A_A") (pintype "passive"))
      (node (ref "EXTRA1") (pin "1") (pinfunction "1_1") (pintype "bidirectional"))
      (node (ref "TPIC0") (pin "15") (pinfunction "Q5_15") (pintype "bidirectional"))
    )
    (net (code "43") (name "/TPIC0_6") (class "Default")
      (node (ref "D29") (pin "A") (pinfunction "A_A") (pintype "passive"))
      (node (ref "EXTRA2") (pin "1") (pinfunction "1_1") (pintype "bidirectional"))
      (node (ref "TPIC0") (pin "16") (pinfunction "Q6_16") (pintype "bidirectional"))
    )
    (net (code "44") (name "/TPIC0_7") (class "Default")
      (node (ref "D30") (pin "A") (pinfunction "A_A") (pintype "passive"))
      (node (ref "EXTRA3") (pin "1") (pinfunction "1_1") (pintype "bidirectional"))
      (node (ref "TPIC0") (pin "17") (pinfunction "Q7_17") (pintype "bidirectional"))
    )
    (net (code "45") (name "/T_DATA") (class "Default")
      (node (ref "B1") (pin "HV4") (pinfunction "HV_TXO_2_HV4") (pintype "bidirectional"))
      (node (ref "TPIC0") (pin "3") (pinfunction "DI_3") (pintype "bidirectional"))
    )
    (net (code "46") (name "/T_DATA1") (class "Default")
      (node (ref "TPIC0") (pin "18") (pinfunction "DO_18") (pintype "bidirectional"))
      (node (ref "TPIC1") (pin "3") (pinfunction "DI_3") (pintype "bidirectional"))
    )
    (net (code "47") (name "/T_DATA2") (class "Default")
      (node (ref "TPIC1") (pin "18") (pinfunction "DO_18") (pintype "bidirectional"))
      (node (ref "TPIC2") (pin "3") (pinfunction "DI_3") (pintype "bidirectional"))
    )
    (net (code "48") (name "/T_DATA3") (class "Default")
      (node (ref "TPIC2") (pin "18") (pinfunction "DO_18") (pintype "bidirectional"))
      (node (ref "TPIC3") (pin "3") (pinfunction "DI_3") (pintype "bidirectional"))
    )
    (net (code "49") (name "/T_RCK") (class "Default")
      (node (ref "B1") (pin "HV2") (pinfunction "HV_RXI_1_HV2") (pintype "bidirectional"))
      (node (ref "TPIC0") (pin "12") (pinfunction "RCK_12") (pintype "bidirectional"))
      (node (ref "TPIC1") (pin "12") (pinfunction "RCK_12") (pintype "bidirectional"))
      (node (ref "TPIC2") (pin "12") (pinfunction "RCK_12") (pintype "bidirectional"))
      (node (ref "TPIC3") (pin "12") (pinfunction "RCK_12") (pintype "bidirectional"))
    )
    (net (code "50") (name "/T_SCK") (class "Default")
      (node (ref "B1") (pin "HV3") (pinfunction "HV_RXI_2_HV3") (pintype "bidirectional"))
      (node (ref "TPIC0") (pin "13") (pinfunction "SCK_13") (pintype "bidirectional"))
      (node (ref "TPIC1") (pin "13") (pinfunction "SCK_13") (pintype "bidirectional"))
      (node (ref "TPIC2") (pin "13") (pinfunction "SCK_13") (pintype "bidirectional"))
      (node (ref "TPIC3") (pin "13") (pinfunction "SCK_13") (pintype "bidirectional"))
    )
    (net (code "51") (name "GND") (class "Default")
      (node (ref "B1") (pin "GND1") (pinfunction "GND_GND1") (pintype "power_in"))
      (node (ref "B1") (pin "GND2") (pinfunction "GND_GND2") (pintype "power_in"))
      (node (ref "C1") (pin "2") (pinfunction "2_2") (pintype "passive"))
      (node (ref "C10") (pin "2") (pinfunction "2_2") (pintype "passive"))
      (node (ref "C11") (pin "2") (pinfunction "2_2") (pintype "passive"))
      (node (ref "C12") (pin "2") (pinfunction "2_2") (pintype "passive"))
      (node (ref "C13") (pin "1") (pinfunction "1_1") (pintype "passive"))
      (node (ref "C14") (pin "1") (pinfunction "1_1") (pintype "passive"))
      (node (ref "C15") (pin "-") (pinfunction "-_-") (pintype "passive"))
      (node (ref "C16") (pin "-") (pinfunction "-_-") (pintype "passive"))
      (node (ref "C17") (pin "2") (pinfunction "2_2") (pintype "passive"))
      (node (ref "C18") (pin "2") (pinfunction "2_2") (pintype "passive"))
      (node (ref "C3") (pin "2") (pinfunction "2_2") (pintype "passive"))
      (node (ref "C4") (pin "2") (pinfunction "2_2") (pintype "passive"))
      (node (ref "C5") (pin "2") (pinfunction "2_2") (pintype "passive"))
      (node (ref "C6") (pin "2") (pinfunction "2_2") (pintype "passive"))
      (node (ref "C7") (pin "-") (pinfunction "-_-") (pintype "passive"))
      (node (ref "C8") (pin "2") (pinfunction "2_2") (pintype "passive"))
      (node (ref "C9") (pin "-") (pinfunction "-_-") (pintype "passive"))
      (node (ref "DRV8871") (pin "1") (pinfunction "GND_1") (pintype "bidirectional"))
      (node (ref "DRV8871") (pin "7") (pinfunction "PGND_7") (pintype "bidirectional"))
      (node (ref "DRV8871") (pin "GND") (pinfunction "GND_GND") (pintype "bidirectional"))
      (node (ref "DRV8871-2") (pin "1") (pinfunction "GND_1") (pintype "bidirectional"))
      (node (ref "DRV8871-2") (pin "7") (pinfunction "PGND_7") (pintype "bidirectional"))
      (node (ref "DRV8871-2") (pin "GND") (pinfunction "GND_GND") (pintype "bidirectional"))
      (node (ref "HEADER") (pin "3") (pinfunction "3_3") (pintype "passive"))
      (node (ref "HEADER") (pin "4") (pinfunction "4_4") (pintype "passive"))
      (node (ref "JP2") (pin "2") (pinfunction "2_2") (pintype "passive"))
      (node (ref "JP2") (pin "4") (pinfunction "4_4") (pintype "passive"))
      (node (ref "NOTGATE1") (pin "3") (pinfunction "GND_3") (pintype "bidirectional"))
      (node (ref "NOTGATE2") (pin "3") (pinfunction "GND_3") (pintype "bidirectional"))
      (node (ref "R1") (pin "1") (pinfunction "1_1") (pintype "passive"))
      (node (ref "R2") (pin "1") (pinfunction "1_1") (pintype "passive"))
      (node (ref "TEST_GND") (pin "1") (pinfunction "1_1") (pintype "passive"))
      (node (ref "TPIC0") (pin "10") (pinfunction "10_10") (pintype "bidirectional"))
      (node (ref "TPIC0") (pin "11") (pinfunction "11_11") (pintype "bidirectional"))
      (node (ref "TPIC0") (pin "19") (pinfunction "19_19") (pintype "bidirectional"))
      (node (ref "TPIC0") (pin "9") (pinfunction "GND_9") (pintype "bidirectional"))
      (node (ref "TPIC1") (pin "10") (pinfunction "10_10") (pintype "bidirectional"))
      (node (ref "TPIC1") (pin "11") (pinfunction "11_11") (pintype "bidirectional"))
      (node (ref "TPIC1") (pin "19") (pinfunction "19_19") (pintype "bidirectional"))
      (node (ref "TPIC1") (pin "9") (pinfunction "GND_9") (pintype "bidirectional"))
      (node (ref "TPIC2") (pin "10") (pinfunction "10_10") (pintype "bidirectional"))
      (node (ref "TPIC2") (pin "11") (pinfunction "11_11") (pintype "bidirectional"))
      (node (ref "TPIC2") (pin "19") (pinfunction "19_19") (pintype "bidirectional"))
      (node (ref "TPIC2") (pin "9") (pinfunction "GND_9") (pintype "bidirectional"))
      (node (ref "TPIC3") (pin "10") (pinfunction "10_10") (pintype "bidirectional"))
      (node (ref "TPIC3") (pin "11") (pinfunction "11_11") (pintype "bidirectional"))
      (node (ref "TPIC3") (pin "19") (pinfunction "19_19") (pintype "bidirectional"))
      (node (ref "TPIC3") (pin "9") (pinfunction "GND_9") (pintype "bidirectional"))
    )
    (net (code "52") (name "Net-(DRV8871-2-ILIM)") (class "Default")
      (node (ref "DRV8871-2") (pin "4") (pinfunction "ILIM_4") (pintype "bidirectional"))
      (node (ref "R2") (pin "2") (pinfunction "2_2") (pintype "passive"))
    )
    (net (code "53") (name "Net-(DRV8871-2-OUT1)") (class "Default")
      (node (ref "DRV8871-2") (pin "6") (pinfunction "OUT1_6") (pintype "bidirectional"))
      (node (ref "LATCHVALVE") (pin "2") (pinfunction "2_2") (pintype "bidirectional"))
    )
    (net (code "54") (name "Net-(DRV8871-2-OUT2)") (class "Default")
      (node (ref "DRV8871-2") (pin "8") (pinfunction "OUT2_8") (pintype "bidirectional"))
      (node (ref "LATCHVALVE") (pin "1") (pinfunction "1_1") (pintype "bidirectional"))
    )
    (net (code "55") (name "Net-(DRV8871-ILIM)") (class "Default")
      (node (ref "DRV8871") (pin "4") (pinfunction "ILIM_4") (pintype "bidirectional"))
      (node (ref "R1") (pin "2") (pinfunction "2_2") (pintype "passive"))
    )
    (net (code "56") (name "unconnected-(B1-HV_TXO_1-PadHV1)") (class "Default")
      (node (ref "B1") (pin "HV1") (pinfunction "HV_TXO_1_HV1") (pintype "bidirectional"))
    )
    (net (code "57") (name "unconnected-(B1-LV_TXI_1-PadLV1)") (class "Default")
      (node (ref "B1") (pin "LV1") (pinfunction "LV_TXI_1_LV1") (pintype "bidirectional"))
    )
    (net (code "58") (name "unconnected-(HEADER-Pad12)") (class "Default")
      (node (ref "HEADER") (pin "12") (pinfunction "12_12") (pintype "passive"))
    )
    (net (code "59") (name "unconnected-(TPIC3-DO-Pad18)") (class "Default")
      (node (ref "TPIC3") (pin "18") (pinfunction "DO_18") (pintype "bidirectional"))
    )
  )
)
